# ArtFire_Status.net
KiCad netlist of a schematic drawn in Altium Designer
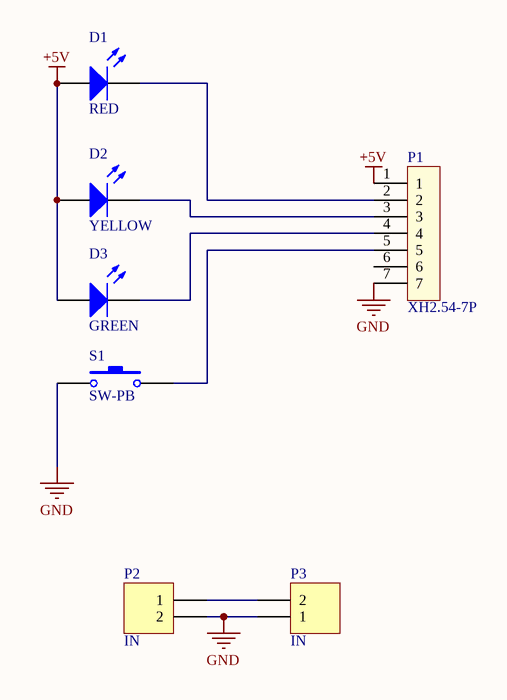
[diagram p0: ArtFire_Status.SchDoc]

(export (version "E")
  (design (tool "Eeschema 10.0.6"))
  (components
    (comp (ref "D1")
      (value "RED")
      (footprint "LED-1")
      (description "Typical RED GaAs LED")
      (fields (field (name "PUBLISHER") "Altium Limited"))
      (libsource (lib "Miscellaneous Devices") (part "LED1"))
    )
    (comp (ref "D2")
      (value "YELLOW")
      (footprint "LED-1")
      (description "Typical RED GaAs LED")
      (fields (field (name "PUBLISHER") "Altium Limited"))
      (libsource (lib "Miscellaneous Devices") (part "LED1"))
    )
    (comp (ref "D3")
      (value "GREEN")
      (footprint "LED-1")
      (description "Typical RED GaAs LED")
      (fields (field (name "PUBLISHER") "Altium Limited"))
      (libsource (lib "Miscellaneous Devices") (part "LED1"))
    )
    (comp (ref "P1")
      (value "XH2.54-7P")
      (footprint "XH2.54-7P")
      (libsource (lib "XH2.54") (part "XH2.54-7P"))
    )
    (comp (ref "P2")
      (value "IN")
      (footprint "ArtFire_Source_Connector")
      (description "Header, 2-Pin")
      (fields (field (name "PUBLISHER") "Altium Limited"))
      (libsource (lib "Miscellaneous Connectors") (part "Header 2"))
    )
    (comp (ref "P3")
      (value "IN")
      (footprint "ArtFire_Source_Connector")
      (description "Header, 2-Pin")
      (fields (field (name "PUBLISHER") "Altium Limited"))
      (libsource (lib "") (part "Header 2_1"))
    )
    (comp (ref "S1")
      (value "SW-PB")
      (footprint "KEY_B")
      (description "Switch")
      (fields (field (name "PUBLISHER") "Altium Limited"))
      (libsource (lib "Miscellaneous Devices") (part "SW-PB"))
    )
  )
  (nets
    (net (code "1") (name "+5V") (class "Default")
      (node (ref "D1") (pin "1") (pinfunction "A_1") (pintype "passive"))
      (node (ref "D2") (pin "1") (pinfunction "A_1") (pintype "passive"))
      (node (ref "D3") (pin "1") (pinfunction "A_1") (pintype "passive"))
      (node (ref "P1") (pin "1") (pinfunction "1_1") (pintype "passive"))
    )
    (net (code "2") (name "GND") (class "Default")
      (node (ref "P1") (pin "7") (pinfunction "7_7") (pintype "passive"))
      (node (ref "P2") (pin "2") (pinfunction "2_2") (pintype "passive"))
      (node (ref "P3") (pin "1") (pinfunction "1_1") (pintype "passive"))
      (node (ref "S1") (pin "1") (pinfunction "1_1") (pintype "passive"))
    )
    (net (code "3") (name "Net-(D1-K)") (class "Default")
      (node (ref "D1") (pin "2") (pinfunction "K_2") (pintype "passive"))
      (node (ref "P1") (pin "2") (pinfunction "2_2") (pintype "passive"))
    )
    (net (code "4") (name "Net-(D2-K)") (class "Default")
      (node (ref "D2") (pin "2") (pinfunction "K_2") (pintype "passive"))
      (node (ref "P1") (pin "3") (pinfunction "3_3") (pintype "passive"))
    )
    (net (code "5") (name "Net-(D3-K)") (class "Default")
      (node (ref "D3") (pin "2") (pinfunction "K_2") (pintype "passive"))
      (node (ref "P1") (pin "4") (pinfunction "4_4") (pintype "passive"))
    )
    (net (code "6") (name "Net-(P1-Pad5)") (class "Default")
      (node (ref "P1") (pin "5") (pinfunction "5_5") (pintype "passive"))
      (node (ref "S1") (pin "2") (pinfunction "2_2") (pintype "passive"))
    )
    (net (code "7") (name "Net-(P2-Pad1)") (class "Default")
      (node (ref "P2") (pin "1") (pinfunction "1_1") (pintype "passive"))
      (node (ref "P3") (pin "2") (pinfunction "2_2") (pintype "passive"))
    )
    (net (code "8") (name "unconnected-(P1-Pad6)") (class "Default")
      (node (ref "P1") (pin "6") (pinfunction "6_6") (pintype "passive"))
    )
  )
)
